# MAIN.net
KiCad netlist of a schematic drawn in Altium Designer
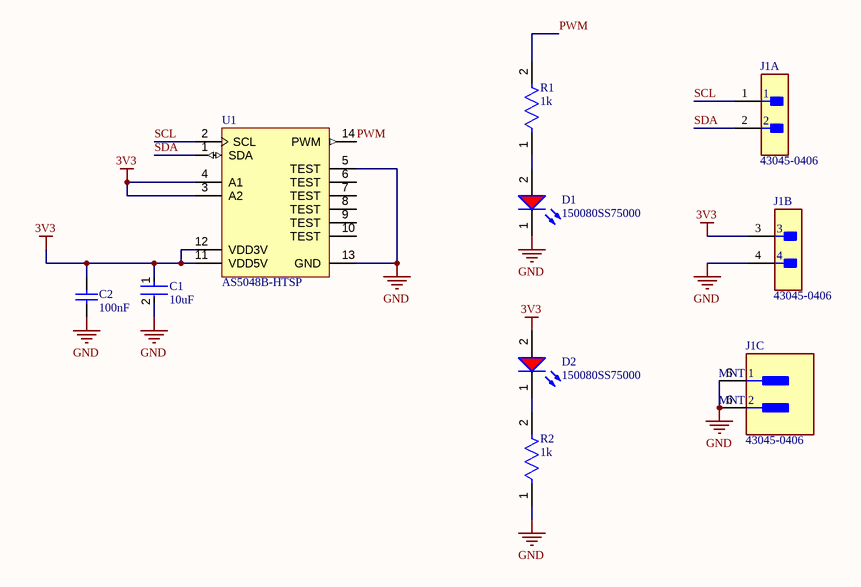
[diagram p0: MAIN.SchDoc]

(export (version "E")
  (design (tool "Eeschema 10.0.6"))
  (components
    (comp (ref "C1")
      (value "10uF")
      (footprint "FP-GRM188-0_1-e0_2_0_55-IPC_A")
      (description "Chip Multilayer Ceramic Capacitors for General Purpose, 0603, 10uF, X5R, 15%, 20%, 6.3V")
      (fields (field (name "VOLTAGE") "6.3V") (field (name "TOLERANCE") "20%"))
      (libsource (lib "Altium Content Vault") (part "02cd4be3c70576c341d710602a673aa"))
    )
    (comp (ref "C2")
      (value "100nF")
      (footprint "CAPC2013X140X50ML20T25")
      (fields
        (field (name "MANUFACTURER") "AVX Interconnect / Elco")
        (field (name "PART NUMBER") "08055F104KAT2A")
      )
      (libsource (lib "Altium Content Vault") (part "CAP"))
    )
    (comp (ref "D1")
      (value "150080SS75000")
      (footprint "WL-SMCW_0805_150080xx75000")
      (description "Led, Red, 630 Nm, 1.9 V, 30 Ma, 60 Mcd Rohs Compliant: Yes")
      (libsource (lib "Altium Content Vault") (part "LED_Red_2A-1K"))
    )
    (comp (ref "D2")
      (value "150080SS75000")
      (footprint "WL-SMCW_0805_150080xx75000")
      (description "Led, Red, 630 Nm, 1.9 V, 30 Ma, 60 Mcd Rohs Compliant: Yes")
      (libsource (lib "Altium Content Vault") (part "LED_Red_2A-1K"))
    )
    (comp (ref "J1")
      (value "43045-0406")
      (footprint "FP-43045-0406-MFG")
      (description "CONN HEADER SMD R/A 4POS 3MM")
      (libsource (lib "Altium Content Vault") (part "58585532e1459b3b5fa8464169874db"))
    )
    (comp (ref "R1")
      (value "1k")
      (footprint "FP-RC0603-0_55-IPC_A")
      (description "RES 1K OHM 1% 1/10W 0603")
      (fields (field (name "TOLERANCE") "1%"))
      (libsource (lib "Altium Content Vault") (part "1029c3af85768c4190bb7ad29bc67b5"))
    )
    (comp (ref "R2")
      (value "1k")
      (footprint "FP-RC0603-0_55-IPC_A")
      (description "RES 1K OHM 1% 1/10W 0603")
      (fields (field (name "TOLERANCE") "1%"))
      (libsource (lib "Altium Content Vault") (part "1029c3af85768c4190bb7ad29bc67b5"))
    )
    (comp (ref "U1")
      (value "AS5048B-HTSP")
      (footprint "AMS-TSSOP-14-5000X4400DE_L")
      (description "Magnetic Rotary Encoder 14-bit Angular Position Sensor, 3.3 or 5 V, TSSOP-14, Pb-Free, Reel")
      (fields (field (name "MANUFACTURER") "AMS"))
      (libsource (lib "Altium Content Vault") (part "AMS-AS5048B-TSSOP-14"))
    )
  )
  (nets
    (net (code "1") (name "/PWM") (class "Default")
      (node (ref "R1") (pin "2") (pinfunction "2_2") (pintype "passive"))
      (node (ref "U1") (pin "14") (pinfunction "PWM_14") (pintype "output"))
    )
    (net (code "2") (name "/SCL") (class "Default")
      (node (ref "J1") (pin "1") (pinfunction "1_1") (pintype "passive"))
      (node (ref "U1") (pin "2") (pinfunction "SCL_2") (pintype "passive"))
    )
    (net (code "3") (name "/SDA") (class "Default")
      (node (ref "J1") (pin "2") (pinfunction "2_2") (pintype "passive"))
      (node (ref "U1") (pin "1") (pinfunction "SDA_1") (pintype "bidirectional"))
    )
    (net (code "4") (name "3V3") (class "Default")
      (node (ref "C1") (pin "1") (pinfunction "1_1") (pintype "passive"))
      (node (ref "C2") (pin "2") (pinfunction "2_2") (pintype "passive"))
      (node (ref "D2") (pin "2") (pinfunction "A_2") (pintype "passive"))
      (node (ref "J1") (pin "3") (pinfunction "3_3") (pintype "passive"))
      (node (ref "U1") (pin "11") (pinfunction "VDD5V_11") (pintype "power_in"))
      (node (ref "U1") (pin "12") (pinfunction "VDD3V_12") (pintype "power_in"))
      (node (ref "U1") (pin "3") (pinfunction "A2_3") (pintype "passive"))
      (node (ref "U1") (pin "4") (pinfunction "A1_4") (pintype "passive"))
    )
    (net (code "5") (name "GND") (class "Default")
      (node (ref "C1") (pin "2") (pinfunction "2_2") (pintype "passive"))
      (node (ref "C2") (pin "1") (pinfunction "1_1") (pintype "passive"))
      (node (ref "D1") (pin "1") (pinfunction "K_1") (pintype "passive"))
      (node (ref "J1") (pin "4") (pinfunction "4_4") (pintype "passive"))
      (node (ref "J1") (pin "5") (pinfunction "MNT_1_5") (pintype "passive"))
      (node (ref "J1") (pin "6") (pinfunction "MNT_2_6") (pintype "passive"))
      (node (ref "R2") (pin "1") (pinfunction "1_1") (pintype "passive"))
      (node (ref "U1") (pin "13") (pinfunction "GND_13") (pintype "power_in"))
      (node (ref "U1") (pin "5") (pinfunction "TEST_5") (pintype "passive"))
    )
    (net (code "6") (name "Net-(D1-A)") (class "Default")
      (node (ref "D1") (pin "2") (pinfunction "A_2") (pintype "passive"))
      (node (ref "R1") (pin "1") (pinfunction "1_1") (pintype "passive"))
    )
    (net (code "7") (name "Net-(D2-K)") (class "Default")
      (node (ref "D2") (pin "1") (pinfunction "K_1") (pintype "passive"))
      (node (ref "R2") (pin "2") (pinfunction "2_2") (pintype "passive"))
    )
    (net (code "8") (name "unconnected-(U1-TEST-Pad6)") (class "Default")
      (node (ref "U1") (pin "6") (pinfunction "TEST_6") (pintype "passive"))
    )
    (net (code "9") (name "unconnected-(U1-TEST-Pad7)") (class "Default")
      (node (ref "U1") (pin "7") (pinfunction "TEST_7") (pintype "passive"))
    )
    (net (code "10") (name "unconnected-(U1-TEST-Pad8)") (class "Default")
      (node (ref "U1") (pin "8") (pinfunction "TEST_8") (pintype "passive"))
    )
    (net (code "11") (name "unconnected-(U1-TEST-Pad9)") (class "Default")
      (node (ref "U1") (pin "9") (pinfunction "TEST_9") (pintype "passive"))
    )
    (net (code "12") (name "unconnected-(U1-TEST-Pad10)") (class "Default")
      (node (ref "U1") (pin "10") (pinfunction "TEST_10") (pintype "passive"))
    )
  )
)
